# PowerCircuit.net
KiCad netlist of a schematic drawn in Altium Designer
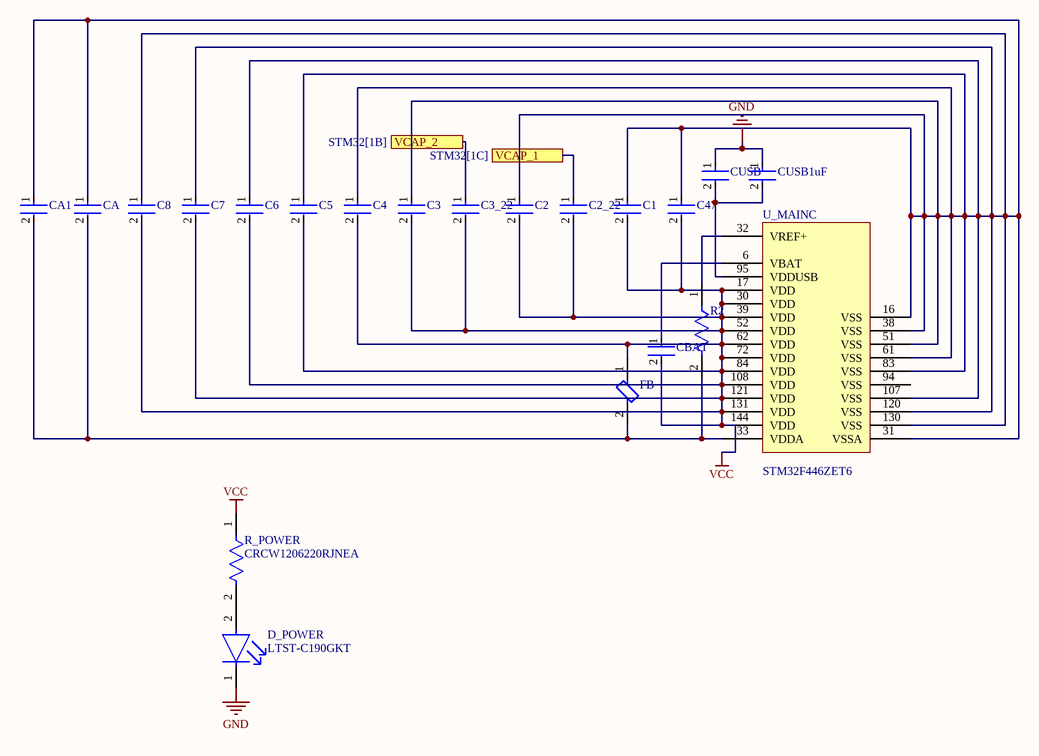
[diagram p0: PowerCircuit.SchDoc]

(export (version "E")
  (design (tool "Eeschema 10.0.6"))
  (components
    (comp (ref "C1")
      (value "GCM155L81E104KE02D")
      (footprint "FP-GCM155-0_05-IPC_B")
      (description "Ceramic Capacitor for Automotive 100nF ±10% 25VDC X8L 0402 Paper T/R")
      (libsource (lib "Altium Content Vault") (part "02cd4be3c70576c341d710602a673aa"))
    )
    (comp (ref "C2")
      (value "GCM155L81E104KE02D")
      (footprint "FP-GCM155-0_05-IPC_B")
      (description "Ceramic Capacitor for Automotive 100nF ±10% 25VDC X8L 0402 Paper T/R")
      (libsource (lib "Altium Content Vault") (part "02cd4be3c70576c341d710602a673aa"))
    )
    (comp (ref "C2_22")
      (value "GRM155R61E225ME15D")
      (footprint "FP-GRM155-0_2-0_05-MFG")
      (description "Chip Multilayer Ceramic Capacitors for General Purpose, 0402, 2.2uF, X5R, 15%, 20%, 25V")
      (fields (field (name "TOLERANCE") "20%"))
      (libsource (lib "Altium Content Vault") (part "b4654b650e69147ec39a6b967a45e02"))
    )
    (comp (ref "C3")
      (value "GCM155L81E104KE02D")
      (footprint "FP-GCM155-0_05-IPC_B")
      (description "Ceramic Capacitor for Automotive 100nF ±10% 25VDC X8L 0402 Paper T/R")
      (libsource (lib "Altium Content Vault") (part "02cd4be3c70576c341d710602a673aa"))
    )
    (comp (ref "C3_22")
      (value "GRM155R61E225ME15D")
      (footprint "FP-GRM155-0_2-0_05-MFG")
      (description "Chip Multilayer Ceramic Capacitors for General Purpose, 0402, 2.2uF, X5R, 15%, 20%, 25V")
      (fields (field (name "TOLERANCE") "20%"))
      (libsource (lib "Altium Content Vault") (part "b4654b650e69147ec39a6b967a45e02"))
    )
    (comp (ref "C4")
      (value "GCM155L81E104KE02D")
      (footprint "FP-GCM155-0_05-IPC_B")
      (description "Ceramic Capacitor for Automotive 100nF ±10% 25VDC X8L 0402 Paper T/R")
      (libsource (lib "Altium Content Vault") (part "02cd4be3c70576c341d710602a673aa"))
    )
    (comp (ref "C5")
      (value "GCM155L81E104KE02D")
      (footprint "FP-GCM155-0_05-IPC_B")
      (description "Ceramic Capacitor for Automotive 100nF ±10% 25VDC X8L 0402 Paper T/R")
      (libsource (lib "Altium Content Vault") (part "02cd4be3c70576c341d710602a673aa"))
    )
    (comp (ref "C6")
      (value "GCM155L81E104KE02D")
      (footprint "FP-GCM155-0_05-IPC_B")
      (description "Ceramic Capacitor for Automotive 100nF ±10% 25VDC X8L 0402 Paper T/R")
      (libsource (lib "Altium Content Vault") (part "02cd4be3c70576c341d710602a673aa"))
    )
    (comp (ref "C7")
      (value "GCM155L81E104KE02D")
      (footprint "FP-GCM155-0_05-IPC_B")
      (description "Ceramic Capacitor for Automotive 100nF ±10% 25VDC X8L 0402 Paper T/R")
      (libsource (lib "Altium Content Vault") (part "02cd4be3c70576c341d710602a673aa"))
    )
    (comp (ref "C8")
      (value "GCM155L81E104KE02D")
      (footprint "FP-GCM155-0_05-IPC_B")
      (description "Ceramic Capacitor for Automotive 100nF ±10% 25VDC X8L 0402 Paper T/R")
      (libsource (lib "Altium Content Vault") (part "02cd4be3c70576c341d710602a673aa"))
    )
    (comp (ref "C47")
      (value "GRM188R61C475KE11D")
      (footprint "FP-GRM188-0_15-MFG")
      (description "Chip Multilayer Ceramic Capacitors for General Purpose, 0603, 4.7uF, X5R, 15%, 10%, 16V")
      (fields (field (name "TOLERANCE") "10%"))
      (libsource (lib "Altium Content Vault") (part "02cd4be3c70576c341d710602a673aa"))
    )
    (comp (ref "CA")
      (value "GCM155L81E104KE02D")
      (footprint "FP-GCM155-0_05-IPC_B")
      (description "Ceramic Capacitor for Automotive 100nF ±10% 25VDC X8L 0402 Paper T/R")
      (libsource (lib "Altium Content Vault") (part "02cd4be3c70576c341d710602a673aa"))
    )
    (comp (ref "CA1")
      (value "GRM155R61C105KA12D")
      (footprint "FP-GRM155-0_05-IPC_C")
      (description "Chip Multilayer Ceramic Capacitors for General Purpose, 0402, 1.0uF, X5R, 15%, 10%, 16V")
      (fields (field (name "VOLTAGE") "16V") (field (name "TOLERANCE") "10%"))
      (libsource (lib "Altium Content Vault") (part "02cd4be3c70576c341d710602a673aa"))
    )
    (comp (ref "CBAT")
      (value "GCM155L81E104KE02D")
      (footprint "FP-GCM155-0_05-IPC_B")
      (description "Ceramic Capacitor for Automotive 100nF ±10% 25VDC X8L 0402 Paper T/R")
      (libsource (lib "Altium Content Vault") (part "02cd4be3c70576c341d710602a673aa"))
    )
    (comp (ref "CUSB")
      (value "GCM155L81E104KE02D")
      (footprint "FP-GCM155-0_05-IPC_B")
      (description "Ceramic Capacitor for Automotive 100nF ±10% 25VDC X8L 0402 Paper T/R")
      (libsource (lib "Altium Content Vault") (part "02cd4be3c70576c341d710602a673aa"))
    )
    (comp (ref "CUSB1uF")
      (value "GCM155L81E104KE02D")
      (footprint "FP-GCM155-0_05-IPC_B")
      (description "Ceramic Capacitor for Automotive 100nF ±10% 25VDC X8L 0402 Paper T/R")
      (libsource (lib "Altium Content Vault") (part "02cd4be3c70576c341d710602a673aa"))
    )
    (comp (ref "D_POWER")
      (value "LTST-C190GKT")
      (footprint "FP-LTST-C190GKT-MFG")
      (description "LED GREEN CLEAR CHIP SMD")
      (fields (field (name "VOLTAGE") "2V"))
      (libsource (lib "Altium Content Vault") (part "8706943c75ba83719d021d2fdc84c58"))
    )
    (comp (ref "FB")
      (value "BLM15AX601SN1D")
      (footprint "FP-BLM15-0_05-IPC_B")
      (description "Chip Ferrite Bead, 0402, 600Ω @ 100MHz, 0.34Ω, 25%, 500mA")
      (fields (field (name "TOLERANCE") "25%"))
      (libsource (lib "Altium Content Vault") (part "5f30dd21d616792df468990f7003faa"))
    )
    (comp (ref "R2")
      (value "RMCF0201ZT0R00")
      (footprint "FP-RMCF0201-IPC_C")
      (description "0Ω ±0 0.05W 0201 Thick Film Chip Resistor AEC-Q200 compliant")
      (libsource (lib "Altium Content Vault") (part "1029c3af85768c4190bb7ad29bc67b5"))
    )
    (comp (ref "R_POWER")
      (value "CRCW1206220RJNEA")
      (footprint "FP-CRCW1206-e3-IPC_C")
      (description "RES Thick Film, 220Ω, 5%, 0.25W, 200ppm/°C, 1206")
      (fields (field (name "TOLERANCE") "5%"))
      (libsource (lib "Altium Content Vault") (part "1029c3af85768c4190bb7ad29bc67b5"))
    )
    (comp (ref "U_MAIN")
      (value "STM32F446ZET6")
      (footprint "STM-LQFP144_M")
      (libsource (lib "Altium Content Vault") (part "MC-ARM-STM32F446-LQFP144"))
    )
  )
  (nets
    (net (code "1") (name "/VCAP_1") (class "Default")
      (node (ref "C2_22") (pin "1") (pinfunction "1_1") (pintype "passive"))
    )
    (net (code "2") (name "/VCAP_2") (class "Default")
      (node (ref "C3_22") (pin "1") (pinfunction "1_1") (pintype "passive"))
    )
    (net (code "3") (name "GND") (class "Default")
      (node (ref "CUSB") (pin "1") (pinfunction "1_1") (pintype "passive"))
      (node (ref "CUSB1uF") (pin "1") (pinfunction "1_1") (pintype "passive"))
      (node (ref "D_POWER") (pin "1") (pinfunction "C_1") (pintype "passive"))
    )
    (net (code "4") (name "Net-(D_POWER-A)") (class "Default")
      (node (ref "D_POWER") (pin "2") (pinfunction "A_2") (pintype "passive"))
      (node (ref "R_POWER") (pin "2") (pinfunction "2_2") (pintype "passive"))
    )
    (net (code "5") (name "Net-(U_MAINC-VBAT)") (class "Default")
      (node (ref "CBAT") (pin "1") (pinfunction "1_1") (pintype "passive"))
      (node (ref "U_MAIN") (pin "6") (pinfunction "VBAT_6") (pintype "power_in"))
    )
    (net (code "6") (name "Net-(U_MAINC-VDDA)") (class "Default")
      (node (ref "CA") (pin "2") (pinfunction "2_2") (pintype "passive"))
      (node (ref "CA1") (pin "2") (pinfunction "2_2") (pintype "passive"))
      (node (ref "FB") (pin "2") (pinfunction "2_2") (pintype "passive"))
      (node (ref "R2") (pin "2") (pinfunction "2_2") (pintype "passive"))
      (node (ref "U_MAIN") (pin "33") (pinfunction "VDDA_33") (pintype "power_in"))
    )
    (net (code "7") (name "Net-(U_MAINC-VDDUSB)") (class "Default")
      (node (ref "CUSB") (pin "2") (pinfunction "2_2") (pintype "passive"))
      (node (ref "CUSB1uF") (pin "2") (pinfunction "2_2") (pintype "passive"))
      (node (ref "U_MAIN") (pin "95") (pinfunction "VDDUSB_95") (pintype "power_in"))
    )
    (net (code "8") (name "Net-(U_MAINC-VREF+)") (class "Default")
      (node (ref "R2") (pin "1") (pinfunction "1_1") (pintype "passive"))
      (node (ref "U_MAIN") (pin "32") (pinfunction "VREF+_32") (pintype "power_in"))
    )
    (net (code "9") (name "Net-(U_MAINC-VSSA)") (class "Default")
      (node (ref "C1") (pin "1") (pinfunction "1_1") (pintype "passive"))
      (node (ref "C2") (pin "1") (pinfunction "1_1") (pintype "passive"))
      (node (ref "C3") (pin "1") (pinfunction "1_1") (pintype "passive"))
      (node (ref "C4") (pin "1") (pinfunction "1_1") (pintype "passive"))
      (node (ref "C47") (pin "1") (pinfunction "1_1") (pintype "passive"))
      (node (ref "C5") (pin "1") (pinfunction "1_1") (pintype "passive"))
      (node (ref "C6") (pin "1") (pinfunction "1_1") (pintype "passive"))
      (node (ref "C7") (pin "1") (pinfunction "1_1") (pintype "passive"))
      (node (ref "C8") (pin "1") (pinfunction "1_1") (pintype "passive"))
      (node (ref "CA") (pin "1") (pinfunction "1_1") (pintype "passive"))
      (node (ref "CA1") (pin "1") (pinfunction "1_1") (pintype "passive"))
      (node (ref "U_MAIN") (pin "107") (pinfunction "VSS_107") (pintype "power_in"))
      (node (ref "U_MAIN") (pin "120") (pinfunction "VSS_120") (pintype "power_in"))
      (node (ref "U_MAIN") (pin "130") (pinfunction "VSS_130") (pintype "power_in"))
      (node (ref "U_MAIN") (pin "16") (pinfunction "VSS_16") (pintype "power_in"))
      (node (ref "U_MAIN") (pin "31") (pinfunction "VSSA_31") (pintype "power_in"))
      (node (ref "U_MAIN") (pin "38") (pinfunction "VSS_38") (pintype "power_in"))
      (node (ref "U_MAIN") (pin "51") (pinfunction "VSS_51") (pintype "power_in"))
      (node (ref "U_MAIN") (pin "61") (pinfunction "VSS_61") (pintype "power_in"))
      (node (ref "U_MAIN") (pin "83") (pinfunction "VSS_83") (pintype "power_in"))
    )
    (net (code "10") (name "VCC") (class "Default")
      (node (ref "C1") (pin "2") (pinfunction "2_2") (pintype "passive"))
      (node (ref "C2") (pin "2") (pinfunction "2_2") (pintype "passive"))
      (node (ref "C2_22") (pin "2") (pinfunction "2_2") (pintype "passive"))
      (node (ref "C3") (pin "2") (pinfunction "2_2") (pintype "passive"))
      (node (ref "C3_22") (pin "2") (pinfunction "2_2") (pintype "passive"))
      (node (ref "C4") (pin "2") (pinfunction "2_2") (pintype "passive"))
      (node (ref "C47") (pin "2") (pinfunction "2_2") (pintype "passive"))
      (node (ref "C5") (pin "2") (pinfunction "2_2") (pintype "passive"))
      (node (ref "C6") (pin "2") (pinfunction "2_2") (pintype "passive"))
      (node (ref "C7") (pin "2") (pinfunction "2_2") (pintype "passive"))
      (node (ref "C8") (pin "2") (pinfunction "2_2") (pintype "passive"))
      (node (ref "CBAT") (pin "2") (pinfunction "2_2") (pintype "passive"))
      (node (ref "FB") (pin "1") (pinfunction "1_1") (pintype "passive"))
      (node (ref "R_POWER") (pin "1") (pinfunction "1_1") (pintype "passive"))
      (node (ref "U_MAIN") (pin "108") (pinfunction "VDD_108") (pintype "power_in"))
      (node (ref "U_MAIN") (pin "121") (pinfunction "VDD_121") (pintype "power_in"))
      (node (ref "U_MAIN") (pin "131") (pinfunction "VDD_131") (pintype "power_in"))
      (node (ref "U_MAIN") (pin "144") (pinfunction "VDD_144") (pintype "power_in"))
      (node (ref "U_MAIN") (pin "17") (pinfunction "VDD_17") (pintype "power_in"))
      (node (ref "U_MAIN") (pin "30") (pinfunction "VDD_30") (pintype "power_in"))
      (node (ref "U_MAIN") (pin "39") (pinfunction "VDD_39") (pintype "power_in"))
      (node (ref "U_MAIN") (pin "52") (pinfunction "VDD_52") (pintype "power_in"))
      (node (ref "U_MAIN") (pin "62") (pinfunction "VDD_62") (pintype "power_in"))
      (node (ref "U_MAIN") (pin "72") (pinfunction "VDD_72") (pintype "power_in"))
      (node (ref "U_MAIN") (pin "84") (pinfunction "VDD_84") (pintype "power_in"))
    )
    (net (code "11") (name "unconnected-(U_MAINC-VSS-Pad94)") (class "Default")
      (node (ref "U_MAIN") (pin "94") (pinfunction "VSS_94") (pintype "power_in"))
    )
  )
)
